# raspi.net
KiCad netlist of a schematic drawn in Altium Designer
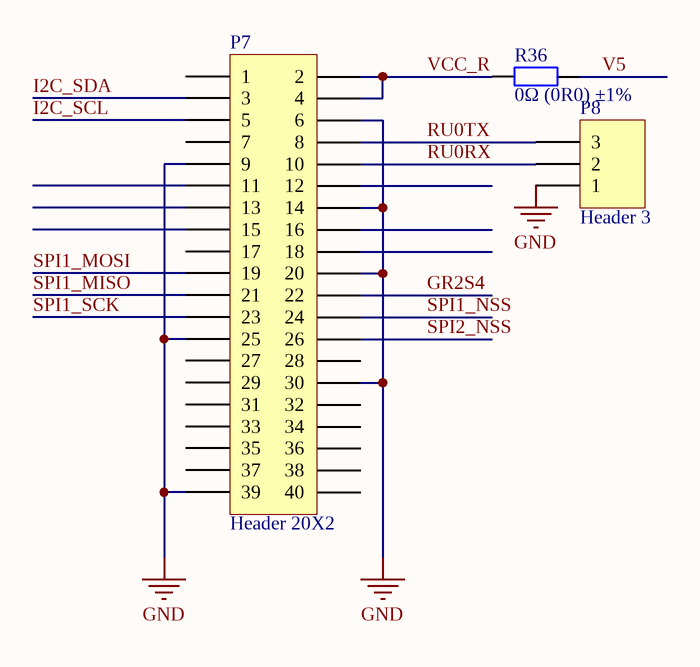
[diagram p0: raspi.SchDoc]

(export (version "E")
  (design (tool "Eeschema 10.0.6"))
  (components
    (comp (ref "P7")
      (value "Header 20X2")
      (footprint "HDR2X20")
      (description "Header, 20-Pin, Dual row")
      (fields (field (name "PUBLISHER") "Altium Limited"))
      (libsource (lib "Miscellaneous Connectors") (part "Header 20X2"))
    )
    (comp (ref "P8")
      (value "Header 3")
      (footprint "HDR1X3")
      (description "Header, 3-Pin")
      (fields (field (name "PUBLISHER") "Altium Limited"))
      (libsource (lib "Miscellaneous Connectors") (part "Header 3"))
    )
    (comp (ref "R36")
      (value "0Ω (0R0) ±1%")
      (footprint "1206_R")
      (description "贴片电阻")
      (libsource (lib "Miscellaneous Devices LC") (part "1206 0Ω (0R0) 1%"))
    )
  )
  (nets
    (net (code "1") (name "/GR2S4") (class "Default")
      (node (ref "P7") (pin "22") (pinfunction "22_22") (pintype "passive"))
    )
    (net (code "2") (name "/I2C_SCL") (class "Default")
      (node (ref "P7") (pin "5") (pinfunction "5_5") (pintype "passive"))
    )
    (net (code "3") (name "/I2C_SDA") (class "Default")
      (node (ref "P7") (pin "3") (pinfunction "3_3") (pintype "passive"))
    )
    (net (code "4") (name "/RU0RX") (class "Default")
      (node (ref "P7") (pin "10") (pinfunction "10_10") (pintype "passive"))
      (node (ref "P8") (pin "2") (pinfunction "2_2") (pintype "passive"))
    )
    (net (code "5") (name "/RU0TX") (class "Default")
      (node (ref "P7") (pin "8") (pinfunction "8_8") (pintype "passive"))
      (node (ref "P8") (pin "3") (pinfunction "3_3") (pintype "passive"))
    )
    (net (code "6") (name "/SPI1_MISO") (class "Default")
      (node (ref "P7") (pin "21") (pinfunction "21_21") (pintype "passive"))
    )
    (net (code "7") (name "/SPI1_MOSI") (class "Default")
      (node (ref "P7") (pin "19") (pinfunction "19_19") (pintype "passive"))
    )
    (net (code "8") (name "/SPI1_NSS") (class "Default")
      (node (ref "P7") (pin "24") (pinfunction "24_24") (pintype "passive"))
    )
    (net (code "9") (name "/SPI1_SCK") (class "Default")
      (node (ref "P7") (pin "23") (pinfunction "23_23") (pintype "passive"))
    )
    (net (code "10") (name "/SPI2_NSS") (class "Default")
      (node (ref "P7") (pin "26") (pinfunction "26_26") (pintype "passive"))
    )
    (net (code "11") (name "/V5") (class "Default")
      (node (ref "R36") (pin "2") (pinfunction "2_2") (pintype "passive"))
    )
    (net (code "12") (name "/VCC_R") (class "Default")
      (node (ref "P7") (pin "2") (pinfunction "2_2") (pintype "passive"))
      (node (ref "P7") (pin "4") (pinfunction "4_4") (pintype "passive"))
      (node (ref "R36") (pin "1") (pinfunction "1_1") (pintype "passive"))
    )
    (net (code "13") (name "GND") (class "Default")
      (node (ref "P7") (pin "14") (pinfunction "14_14") (pintype "passive"))
      (node (ref "P7") (pin "20") (pinfunction "20_20") (pintype "passive"))
      (node (ref "P7") (pin "25") (pinfunction "25_25") (pintype "passive"))
      (node (ref "P7") (pin "30") (pinfunction "30_30") (pintype "passive"))
      (node (ref "P7") (pin "39") (pinfunction "39_39") (pintype "passive"))
      (node (ref "P7") (pin "6") (pinfunction "6_6") (pintype "passive"))
      (node (ref "P7") (pin "9") (pinfunction "9_9") (pintype "passive"))
      (node (ref "P8") (pin "1") (pinfunction "1_1") (pintype "passive"))
    )
    (net (code "14") (name "unconnected-(P7-Pad1)") (class "Default")
      (node (ref "P7") (pin "1") (pinfunction "1_1") (pintype "passive"))
    )
    (net (code "15") (name "unconnected-(P7-Pad7)") (class "Default")
      (node (ref "P7") (pin "7") (pinfunction "7_7") (pintype "passive"))
    )
    (net (code "16") (name "unconnected-(P7-Pad11)") (class "Default")
      (node (ref "P7") (pin "11") (pinfunction "11_11") (pintype "passive"))
    )
    (net (code "17") (name "unconnected-(P7-Pad12)") (class "Default")
      (node (ref "P7") (pin "12") (pinfunction "12_12") (pintype "passive"))
    )
    (net (code "18") (name "unconnected-(P7-Pad13)") (class "Default")
      (node (ref "P7") (pin "13") (pinfunction "13_13") (pintype "passive"))
    )
    (net (code "19") (name "unconnected-(P7-Pad15)") (class "Default")
      (node (ref "P7") (pin "15") (pinfunction "15_15") (pintype "passive"))
    )
    (net (code "20") (name "unconnected-(P7-Pad16)") (class "Default")
      (node (ref "P7") (pin "16") (pinfunction "16_16") (pintype "passive"))
    )
    (net (code "21") (name "unconnected-(P7-Pad17)") (class "Default")
      (node (ref "P7") (pin "17") (pinfunction "17_17") (pintype "passive"))
    )
    (net (code "22") (name "unconnected-(P7-Pad18)") (class "Default")
      (node (ref "P7") (pin "18") (pinfunction "18_18") (pintype "passive"))
    )
    (net (code "23") (name "unconnected-(P7-Pad27)") (class "Default")
      (node (ref "P7") (pin "27") (pinfunction "27_27") (pintype "passive"))
    )
    (net (code "24") (name "unconnected-(P7-Pad28)") (class "Default")
      (node (ref "P7") (pin "28") (pinfunction "28_28") (pintype "passive"))
    )
    (net (code "25") (name "unconnected-(P7-Pad29)") (class "Default")
      (node (ref "P7") (pin "29") (pinfunction "29_29") (pintype "passive"))
    )
    (net (code "26") (name "unconnected-(P7-Pad31)") (class "Default")
      (node (ref "P7") (pin "31") (pinfunction "31_31") (pintype "passive"))
    )
    (net (code "27") (name "unconnected-(P7-Pad32)") (class "Default")
      (node (ref "P7") (pin "32") (pinfunction "32_32") (pintype "passive"))
    )
    (net (code "28") (name "unconnected-(P7-Pad33)") (class "Default")
      (node (ref "P7") (pin "33") (pinfunction "33_33") (pintype "passive"))
    )
    (net (code "29") (name "unconnected-(P7-Pad34)") (class "Default")
      (node (ref "P7") (pin "34") (pinfunction "34_34") (pintype "passive"))
    )
    (net (code "30") (name "unconnected-(P7-Pad35)") (class "Default")
      (node (ref "P7") (pin "35") (pinfunction "35_35") (pintype "passive"))
    )
    (net (code "31") (name "unconnected-(P7-Pad36)") (class "Default")
      (node (ref "P7") (pin "36") (pinfunction "36_36") (pintype "passive"))
    )
    (net (code "32") (name "unconnected-(P7-Pad37)") (class "Default")
      (node (ref "P7") (pin "37") (pinfunction "37_37") (pintype "passive"))
    )
    (net (code "33") (name "unconnected-(P7-Pad38)") (class "Default")
      (node (ref "P7") (pin "38") (pinfunction "38_38") (pintype "passive"))
    )
    (net (code "34") (name "unconnected-(P7-Pad40)") (class "Default")
      (node (ref "P7") (pin "40") (pinfunction "40_40") (pintype "passive"))
    )
  )
)
